# nguyenly.net
KiCad netlist of a schematic drawn in Altium Designer
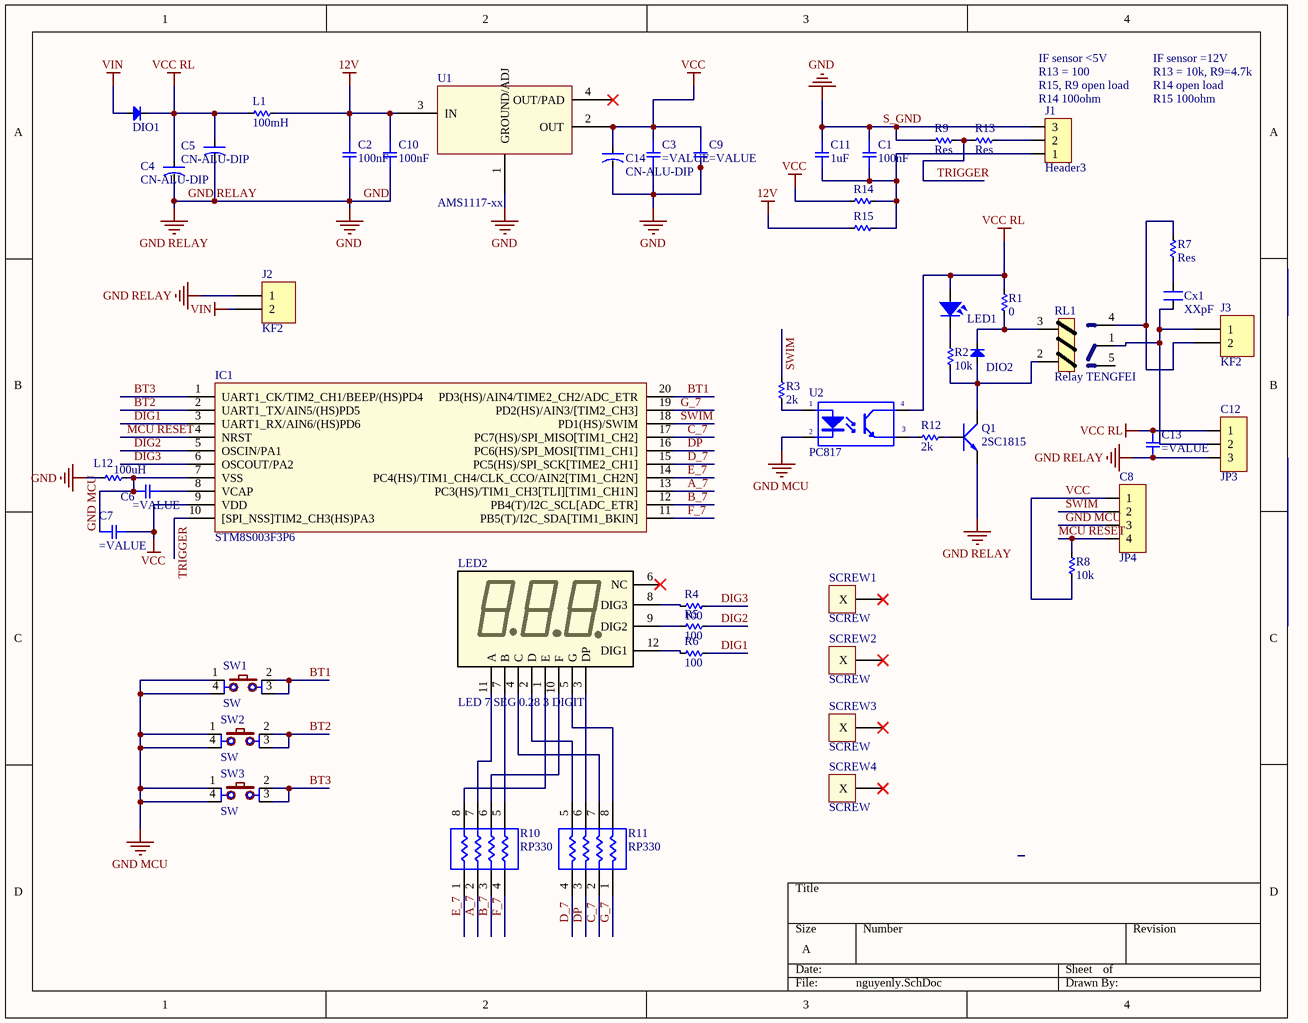
[diagram p0: nguyenly.SchDoc]

(export (version "E")
  (design (tool "Eeschema 10.0.6"))
  (components
    (comp (ref "C1")
      (value "100nF")
      (footprint "SMD-0805C")
      (description "CAP MLCC SMT")
      (libsource (lib "HOANG_ANH") (part "CAPACITOR"))
    )
    (comp (ref "C2")
      (value "100nF")
      (footprint "SMD-0805C")
      (description "CAP MLCC SMT")
      (libsource (lib "HOANG_ANH") (part "CAPACITOR"))
    )
    (comp (ref "C3")
      (value "~")
      (footprint "SMD-0805C")
      (description "CAP MLCC SMT")
      (libsource (lib "HOANG_ANH") (part "CAPACITOR"))
    )
    (comp (ref "C4")
      (value "CN-ALU-DIP")
      (footprint "CA-ALU-8")
      (description "Capacitor (Semiconductor SIM Model)")
      (fields (field (name "PUBLISHER") "Altium Limited"))
      (libsource (lib "LIBRARY") (part "CN-ALU-DIP"))
    )
    (comp (ref "C5")
      (value "CN-ALU-DIP")
      (footprint "CA-ALU-8")
      (description "Capacitor (Semiconductor SIM Model)")
      (fields (field (name "PUBLISHER") "Altium Limited"))
      (libsource (lib "LIBRARY") (part "CN-ALU-DIP"))
    )
    (comp (ref "C6")
      (value "~")
      (footprint "SMD-0805C")
      (description "CAP MLCC SMT")
      (libsource (lib "HOANG_ANH") (part "CAPACITOR"))
    )
    (comp (ref "C7")
      (value "~")
      (footprint "SMD-0805C")
      (description "CAP MLCC SMT")
      (libsource (lib "HOANG_ANH") (part "CAPACITOR"))
    )
    (comp (ref "C8")
      (value "JP4")
      (footprint "JP4-C1T")
      (description "WR-PHD 2.54 mm Angled Socket Header")
      (fields
        (field (name "MANUFACTURER") "Würth Elektronik eiSos GmbH")
        (field (name "PARTNO") "613004143121")
        (field (name "CREATED BY") "Karrer Zheng")
      )
      (libsource (lib "LIBRARY") (part "JP4"))
    )
    (comp (ref "C9")
      (value "~")
      (footprint "SMD-0805C")
      (description "CAP MLCC SMT")
      (libsource (lib "HOANG_ANH") (part "CAPACITOR"))
    )
    (comp (ref "C10")
      (value "100nF")
      (footprint "SMD-0805C")
      (description "CAP MLCC SMT")
      (libsource (lib "HOANG_ANH") (part "CAPACITOR"))
    )
    (comp (ref "C11")
      (value "1uF")
      (footprint "SMD-0805C")
      (description "CAP MLCC SMT")
      (libsource (lib "HOANG_ANH") (part "CAPACITOR"))
    )
    (comp (ref "C12")
      (value "JP3")
      (footprint "JP3-CLOSED")
      (description "WR-PHD 2.54 mm Angled Socket Header")
      (fields
        (field (name "MANUFACTURER") "Würth Elektronik eiSos GmbH")
        (field (name "PARTNO") "613003143121")
        (field (name "CREATED BY") "Karrer Zheng")
      )
      (libsource (lib "LIBRARY") (part "JP3"))
    )
    (comp (ref "C13")
      (value "~")
      (footprint "SMD-1812 FUSE")
      (description "CAP MLCC SMT")
      (libsource (lib "HOANG_ANH") (part "CAPACITOR"))
    )
    (comp (ref "C14")
      (value "CN-ALU-DIP")
      (footprint "CA-ALU-2.54")
      (description "Capacitor (Semiconductor SIM Model)")
      (fields (field (name "PUBLISHER") "Altium Limited"))
      (libsource (lib "LIBRARY") (part "CN-ALU-DIP"))
    )
    (comp (ref "Cx1") (value "XXpF") (footprint "CN2.5") (libsource (lib "LIBRARY") (part "CN")))
    (comp (ref "DIO1")
      (value "Diode SMD")
      (footprint "DIO-SMD-106")
      (description "Default Diode")
      (fields (field (name "PUBLISHER") "Altium Limited"))
      (libsource (lib "LIBRARY") (part "Diode SMD"))
    )
    (comp (ref "DIO2")
      (value "Diode SMD")
      (footprint "DIO-SMD-106")
      (description "Default Diode")
      (fields (field (name "PUBLISHER") "Altium Limited"))
      (libsource (lib "LIBRARY") (part "Diode SMD"))
    )
    (comp (ref "IC1")
      (value "STM8S003F3P6")
      (footprint "TSSOP20")
      (description "MCU 8BIT  8KB FLASH TSSOP-20")
      (fields (field (name "COPYRIGHT BY") "VanDungEvn"))
      (libsource (lib "LIBRARY") (part "STM8S003F3P6"))
    )
    (comp (ref "J1")
      (value "Header3")
      (footprint "Header3")
      (description "Header IDC, 3 x 1 Pin Vertical 2.54mm Pitch (Non-Boxed, Male)")
      (fields
        (field (name "MANUFACTURER") "Würth Elektronik eiSos GmbH")
        (field (name "PARTNO") "613002143121")
        (field (name "CREATED BY") "Karrer Zheng")
      )
      (libsource (lib "LIBRARY") (part "Header3"))
    )
    (comp (ref "J2")
      (value "KF2")
      (footprint "KF2-5.08")
      (fields
        (field (name "MANUFACTURER") "Würth Elektronik eiSos GmbH")
        (field (name "PARTNO") "691103110002")
        (field (name "CREATED BY") "Karrer Zheng")
      )
      (libsource (lib "LIBRARY") (part "KF2"))
    )
    (comp (ref "J3")
      (value "KF2")
      (footprint "KF2-5.08")
      (fields
        (field (name "MANUFACTURER") "Würth Elektronik eiSos GmbH")
        (field (name "PARTNO") "691103110002")
        (field (name "CREATED BY") "Karrer Zheng")
      )
      (libsource (lib "LIBRARY") (part "KF2"))
    )
    (comp (ref "L1")
      (value "100mH")
      (footprint "RES-SMD-0805")
      (description "Resistor")
      (fields
        (field (name "MANUFACTURER") "Generic Components")
        (field (name "PUBLISHER") "Altium Hobart Technology Centre")
      )
      (libsource (lib "LIBRARY") (part "Res-SMD"))
    )
    (comp (ref "L12")
      (value "100uH")
      (footprint "RES-SMD-0805")
      (description "Resistor")
      (fields
        (field (name "MANUFACTURER") "Generic Components")
        (field (name "PUBLISHER") "Altium Hobart Technology Centre")
      )
      (libsource (lib "LIBRARY") (part "Res-SMD"))
    )
    (comp (ref "LED1")
      (value "LED")
      (footprint "LED-0805-Yellow")
      (libsource (lib "LIBRARY") (part "LED SMD"))
    )
    (comp (ref "LED2")
      (value "LED 7 SEG 0.28 3 DIGIT")
      (footprint "LED 7 Seg 0.28, 3 digit, RED")
      (libsource (lib "HOANG_ANH") (part "LED 7 Segment"))
    )
    (comp (ref "Q1")
      (value "2SC1815")
      (footprint "SOT23-321")
      (description "NPN 600mW, ECB")
      (libsource (lib "LIBRARY") (part "2SC1815"))
    )
    (comp (ref "R1")
      (value "0")
      (footprint "RES-SMD-0805")
      (description "Resistor")
      (fields
        (field (name "MANUFACTURER") "Generic Components")
        (field (name "PUBLISHER") "Altium Hobart Technology Centre")
      )
      (libsource (lib "LIBRARY") (part "Res-SMD"))
    )
    (comp (ref "R2")
      (value "10k")
      (footprint "RES-SMD-0805")
      (description "Resistor")
      (fields
        (field (name "MANUFACTURER") "Generic Components")
        (field (name "PUBLISHER") "Altium Hobart Technology Centre")
      )
      (libsource (lib "LIBRARY") (part "Res-SMD"))
    )
    (comp (ref "R3")
      (value "2k")
      (footprint "RES-SMD-0805")
      (description "Resistor")
      (fields
        (field (name "MANUFACTURER") "Generic Components")
        (field (name "PUBLISHER") "Altium Hobart Technology Centre")
      )
      (libsource (lib "LIBRARY") (part "Res-SMD"))
    )
    (comp (ref "R4")
      (value "100")
      (footprint "RES-SMD-0805")
      (description "Resistor")
      (fields
        (field (name "MANUFACTURER") "Generic Components")
        (field (name "PUBLISHER") "Altium Hobart Technology Centre")
      )
      (libsource (lib "LIBRARY") (part "Res-SMD"))
    )
    (comp (ref "R5")
      (value "100")
      (footprint "RES-SMD-0805")
      (description "Resistor")
      (fields
        (field (name "MANUFACTURER") "Generic Components")
        (field (name "PUBLISHER") "Altium Hobart Technology Centre")
      )
      (libsource (lib "LIBRARY") (part "Res-SMD"))
    )
    (comp (ref "R6")
      (value "100")
      (footprint "RES-SMD-0805")
      (description "Resistor")
      (fields
        (field (name "MANUFACTURER") "Generic Components")
        (field (name "PUBLISHER") "Altium Hobart Technology Centre")
      )
      (libsource (lib "LIBRARY") (part "Res-SMD"))
    )
    (comp (ref "R7")
      (value "Res")
      (footprint "RES-SMD-0805")
      (description "Resistor")
      (fields
        (field (name "MANUFACTURER") "Generic Components")
        (field (name "PUBLISHER") "Altium Hobart Technology Centre")
      )
      (libsource (lib "LIBRARY") (part "Res-SMD"))
    )
    (comp (ref "R8")
      (value "10k")
      (footprint "RES-SMD-0805")
      (description "Resistor")
      (fields
        (field (name "MANUFACTURER") "Generic Components")
        (field (name "PUBLISHER") "Altium Hobart Technology Centre")
      )
      (libsource (lib "LIBRARY") (part "Res-SMD"))
    )
    (comp (ref "R9")
      (value "Res")
      (footprint "RES-SMD-0805")
      (description "Resistor")
      (fields
        (field (name "MANUFACTURER") "Generic Components")
        (field (name "PUBLISHER") "Altium Hobart Technology Centre")
      )
      (libsource (lib "LIBRARY") (part "Res-SMD"))
    )
    (comp (ref "R10") (value "RP330") (footprint "RN4-0805") (libsource (lib "LIBRARY") (part "RN4-Dual")))
    (comp (ref "R11") (value "RP330") (footprint "RN4-0805") (libsource (lib "LIBRARY") (part "RN4-Dual")))
    (comp (ref "R12")
      (value "2k")
      (footprint "RES-SMD-0805")
      (description "Resistor")
      (fields
        (field (name "MANUFACTURER") "Generic Components")
        (field (name "PUBLISHER") "Altium Hobart Technology Centre")
      )
      (libsource (lib "LIBRARY") (part "Res-SMD"))
    )
    (comp (ref "R13")
      (value "Res")
      (footprint "RES-SMD-0805")
      (description "Resistor")
      (fields
        (field (name "MANUFACTURER") "Generic Components")
        (field (name "PUBLISHER") "Altium Hobart Technology Centre")
      )
      (libsource (lib "LIBRARY") (part "Res-SMD"))
    )
    (comp (ref "R14")
      (value "Res")
      (footprint "RES-SMD-0805")
      (description "Resistor")
      (fields
        (field (name "MANUFACTURER") "Generic Components")
        (field (name "PUBLISHER") "Altium Hobart Technology Centre")
      )
      (libsource (lib "LIBRARY") (part "Res-SMD"))
    )
    (comp (ref "R15")
      (value "Res")
      (footprint "RES-SMD-0805")
      (description "Resistor")
      (fields
        (field (name "MANUFACTURER") "Generic Components")
        (field (name "PUBLISHER") "Altium Hobart Technology Centre")
      )
      (libsource (lib "LIBRARY") (part "Res-SMD"))
    )
    (comp (ref "RL1")
      (value "Relay TENGFEI")
      (footprint "JQC-T78-DC12V-A")
      (libsource (lib "HOANG_ANH") (part "Relay TENGFEI"))
    )
    (comp (ref "SCREW1") (value "SCREW") (footprint "SCREW-M5") (libsource (lib "HOANG_ANH") (part "SCREW")))
    (comp (ref "SCREW2") (value "SCREW") (footprint "SCREW-M5") (libsource (lib "HOANG_ANH") (part "SCREW")))
    (comp (ref "SCREW3") (value "SCREW") (footprint "SCREW-M5") (libsource (lib "HOANG_ANH") (part "SCREW")))
    (comp (ref "SCREW4") (value "SCREW") (footprint "SCREW-M5") (libsource (lib "HOANG_ANH") (part "SCREW")))
    (comp (ref "SW1")
      (value "SW")
      (footprint "SW2-DIP")
      (description "Switch button 4 pin")
      (libsource (lib "LIBRARY") (part "SW4"))
    )
    (comp (ref "SW2")
      (value "SW")
      (footprint "SW2-DIP")
      (description "Switch button 4 pin")
      (libsource (lib "LIBRARY") (part "SW4"))
    )
    (comp (ref "SW3")
      (value "SW")
      (footprint "SW2-DIP")
      (description "Switch button 4 pin")
      (libsource (lib "LIBRARY") (part "SW4"))
    )
    (comp (ref "U1")
      (value "AMS1117-xx")
      (footprint "SOT-233")
      (libsource (lib "HOANG_ANH") (part "AMS1117-xx"))
    )
    (comp (ref "U2")
      (value "PC817")
      (footprint "DIP4")
      (description "Single Opto")
      (libsource (lib "LIBRARY") (part "PC817"))
    )
  )
  (nets
    (net (code "1") (name "/A_7") (class "Default")
      (node (ref "IC1") (pin "13") (pinfunction "PC3(HS)/TIM1_CH3[TLI][TIM1_CH1N]_13") (pintype "passive"))
      (node (ref "R10") (pin "2") (pinfunction "2_2") (pintype "passive"))
    )
    (net (code "2") (name "/BT1") (class "Default")
      (node (ref "IC1") (pin "20") (pinfunction "PD3(HS)/AIN4/TIME2_CH2/ADC_ETR_20") (pintype "passive"))
      (node (ref "SW1") (pin "2") (pinfunction "2_2") (pintype "passive"))
      (node (ref "SW1") (pin "3") (pinfunction "3_3") (pintype "passive"))
    )
    (net (code "3") (name "/BT2") (class "Default")
      (node (ref "IC1") (pin "2") (pinfunction "UART1_TX/AIN5/(HS)PD5_2") (pintype "passive"))
      (node (ref "SW2") (pin "2") (pinfunction "2_2") (pintype "passive"))
      (node (ref "SW2") (pin "3") (pinfunction "3_3") (pintype "passive"))
    )
    (net (code "4") (name "/BT3") (class "Default")
      (node (ref "IC1") (pin "1") (pinfunction "UART1_CK/TIM2_CH1/BEEP/(HS)PD4_1") (pintype "passive"))
      (node (ref "SW3") (pin "2") (pinfunction "2_2") (pintype "passive"))
      (node (ref "SW3") (pin "3") (pinfunction "3_3") (pintype "passive"))
    )
    (net (code "5") (name "/B_7") (class "Default")
      (node (ref "IC1") (pin "12") (pinfunction "PB4(T)/I2C_SCL[ADC_ETR]_12") (pintype "passive"))
      (node (ref "R10") (pin "3") (pinfunction "3_3") (pintype "passive"))
    )
    (net (code "6") (name "/C_7") (class "Default")
      (node (ref "IC1") (pin "17") (pinfunction "PC7(HS)/SPI_MISO[TIM1_CH2]_17") (pintype "passive"))
      (node (ref "R11") (pin "2") (pinfunction "2_2") (pintype "passive"))
    )
    (net (code "7") (name "/DIG1") (class "Default")
      (node (ref "IC1") (pin "3") (pinfunction "UART1_RX/AIN6/(HS)PD6_3") (pintype "passive"))
      (node (ref "R6") (pin "1") (pinfunction "1_1") (pintype "passive"))
    )
    (net (code "8") (name "/DIG2") (class "Default")
      (node (ref "IC1") (pin "5") (pinfunction "OSCIN/PA1_5") (pintype "passive"))
      (node (ref "R5") (pin "1") (pinfunction "1_1") (pintype "passive"))
    )
    (net (code "9") (name "/DIG3") (class "Default")
      (node (ref "IC1") (pin "6") (pinfunction "OSCOUT/PA2_6") (pintype "passive"))
      (node (ref "R4") (pin "1") (pinfunction "1_1") (pintype "passive"))
    )
    (net (code "10") (name "/DP") (class "Default")
      (node (ref "IC1") (pin "16") (pinfunction "PC6(HS)/SPI_MOSI[TIM1_CH1]_16") (pintype "passive"))
      (node (ref "R11") (pin "3") (pinfunction "3_3") (pintype "passive"))
    )
    (net (code "11") (name "/D_7") (class "Default")
      (node (ref "IC1") (pin "15") (pinfunction "PC5(HS)/SPI_SCK[TIME2_CH1]_15") (pintype "passive"))
      (node (ref "R11") (pin "4") (pinfunction "4_4") (pintype "passive"))
    )
    (net (code "12") (name "/E_7") (class "Default")
      (node (ref "IC1") (pin "14") (pinfunction "PC4(HS)/TIM1_CH4/CLK_CCO/AIN2[TIM1_CH2N]_14") (pintype "passive"))
      (node (ref "R10") (pin "1") (pinfunction "1_1") (pintype "passive"))
    )
    (net (code "13") (name "/F_7") (class "Default")
      (node (ref "IC1") (pin "11") (pinfunction "PB5(T)/I2C_SDA[TIM1_BKIN]_11") (pintype "passive"))
      (node (ref "R10") (pin "4") (pinfunction "4_4") (pintype "passive"))
    )
    (net (code "14") (name "/G_7") (class "Default")
      (node (ref "IC1") (pin "19") (pinfunction "PD2(HS)/AIN3/[TIM2_CH3]_19") (pintype "passive"))
      (node (ref "R11") (pin "1") (pinfunction "1_1") (pintype "passive"))
    )
    (net (code "15") (name "/MCU RESET") (class "Default")
      (node (ref "C8") (pin "4") (pinfunction "4_4") (pintype "passive"))
      (node (ref "IC1") (pin "4") (pinfunction "NRST_4") (pintype "passive"))
      (node (ref "R8") (pin "2") (pinfunction "2_2") (pintype "passive"))
    )
    (net (code "16") (name "/SWIM") (class "Default")
      (node (ref "C8") (pin "2") (pinfunction "2_2") (pintype "passive"))
      (node (ref "IC1") (pin "18") (pinfunction "PD1(HS)/SWIM_18") (pintype "passive"))
      (node (ref "R3") (pin "2") (pinfunction "2_2") (pintype "passive"))
    )
    (net (code "17") (name "/TRIGGER") (class "Default")
      (node (ref "IC1") (pin "10") (pinfunction "[SPI_NSS]TIM2_CH3(HS)PA3_10") (pintype "passive"))
      (node (ref "R13") (pin "2") (pinfunction "2_2") (pintype "passive"))
      (node (ref "R9") (pin "1") (pinfunction "1_1") (pintype "passive"))
    )
    (net (code "18") (name "12V") (class "Default")
      (node (ref "C10") (pin "1") (pinfunction "1_1") (pintype "passive"))
      (node (ref "C2") (pin "1") (pinfunction "1_1") (pintype "passive"))
      (node (ref "L1") (pin "1") (pinfunction "1_1") (pintype "passive"))
      (node (ref "R15") (pin "2") (pinfunction "2_2") (pintype "passive"))
      (node (ref "U1") (pin "3") (pinfunction "IN_3") (pintype "power_in"))
    )
    (net (code "19") (name "GND") (class "Default")
      (node (ref "C1") (pin "1") (pinfunction "1_1") (pintype "passive"))
      (node (ref "C10") (pin "2") (pinfunction "2_2") (pintype "passive"))
      (node (ref "C11") (pin "1") (pinfunction "1_1") (pintype "passive"))
      (node (ref "C12") (pin "3") (pinfunction "3_3") (pintype "passive"))
      (node (ref "C13") (pin "2") (pinfunction "2_2") (pintype "passive"))
      (node (ref "C14") (pin "2") (pinfunction "2_2") (pintype "passive"))
      (node (ref "C2") (pin "2") (pinfunction "2_2") (pintype "passive"))
      (node (ref "C3") (pin "2") (pinfunction "2_2") (pintype "passive"))
      (node (ref "C4") (pin "2") (pinfunction "2_2") (pintype "passive"))
      (node (ref "C5") (pin "2") (pinfunction "2_2") (pintype "passive"))
      (node (ref "C9") (pin "2") (pinfunction "2_2") (pintype "passive"))
      (node (ref "J1") (pin "3") (pinfunction "3_3") (pintype "passive"))
      (node (ref "J2") (pin "1") (pinfunction "1_1") (pintype "passive"))
      (node (ref "L12") (pin "2") (pinfunction "2_2") (pintype "passive"))
      (node (ref "Q1") (pin "1") (pinfunction "E_1") (pintype "passive"))
      (node (ref "R9") (pin "2") (pinfunction "2_2") (pintype "passive"))
      (node (ref "U1") (pin "1") (pinfunction "GROUND/ADJ_1") (pintype "power_in"))
    )
    (net (code "20") (name "GND MCU") (class "Default")
      (node (ref "C6") (pin "1") (pinfunction "1_1") (pintype "passive"))
      (node (ref "C7") (pin "1") (pinfunction "1_1") (pintype "passive"))
      (node (ref "C8") (pin "3") (pinfunction "3_3") (pintype "passive"))
      (node (ref "IC1") (pin "7") (pinfunction "VSS_7") (pintype "passive"))
      (node (ref "L12") (pin "1") (pinfunction "1_1") (pintype "passive"))
      (node (ref "SW1") (pin "1") (pintype "passive"))
      (node (ref "SW1") (pin "4") (pinfunction "4_4") (pintype "passive"))
      (node (ref "SW2") (pin "1") (pintype "passive"))
      (node (ref "SW2") (pin "4") (pinfunction "4_4") (pintype "passive"))
      (node (ref "SW3") (pin "1") (pintype "passive"))
      (node (ref "SW3") (pin "4") (pinfunction "4_4") (pintype "passive"))
      (node (ref "U2") (pin "2") (pinfunction "K_2") (pintype "passive"))
    )
    (net (code "21") (name "Net-(C1-Pad2)") (class "Default")
      (node (ref "C1") (pin "2") (pinfunction "2_2") (pintype "passive"))
      (node (ref "C11") (pin "2") (pinfunction "2_2") (pintype "passive"))
      (node (ref "J1") (pin "1") (pinfunction "1_1") (pintype "passive"))
      (node (ref "R14") (pin "1") (pinfunction "1_1") (pintype "passive"))
      (node (ref "R15") (pin "1") (pinfunction "1_1") (pintype "passive"))
    )
    (net (code "22") (name "Net-(C12-Pad2)") (class "Default")
      (node (ref "C12") (pin "2") (pinfunction "2_2") (pintype "passive"))
      (node (ref "Cx1") (pin "2") (pinfunction "2_2") (pintype "passive"))
      (node (ref "J3") (pin "1") (pinfunction "1_1") (pintype "passive"))
      (node (ref "RL1") (pin "1") (pinfunction "1_1") (pintype "passive"))
    )
    (net (code "23") (name "Net-(Cx1-Pad1)") (class "Default")
      (node (ref "Cx1") (pin "1") (pinfunction "1_1") (pintype "passive"))
      (node (ref "R7") (pin "2") (pinfunction "2_2") (pintype "passive"))
    )
    (net (code "24") (name "Net-(DIO2-A)") (class "Default")
      (node (ref "DIO2") (pin "1") (pinfunction "A_1") (pintype "passive"))
      (node (ref "Q1") (pin "2") (pinfunction "C_2") (pintype "passive"))
      (node (ref "R2") (pin "2") (pinfunction "2_2") (pintype "passive"))
      (node (ref "RL1") (pin "2") (pinfunction "2_2") (pintype "passive"))
    )
    (net (code "25") (name "Net-(DIO2-K)") (class "Default")
      (node (ref "DIO2") (pin "2") (pinfunction "K_2") (pintype "passive"))
      (node (ref "R1") (pin "1") (pinfunction "1_1") (pintype "passive"))
      (node (ref "RL1") (pin "3") (pinfunction "3_3") (pintype "passive"))
    )
    (net (code "26") (name "Net-(IC1-VCAP)") (class "Default")
      (node (ref "C6") (pin "2") (pinfunction "2_2") (pintype "passive"))
      (node (ref "IC1") (pin "8") (pinfunction "VCAP_8") (pintype "passive"))
    )
    (net (code "27") (name "Net-(J1-Pad2)") (class "Default")
      (node (ref "J1") (pin "2") (pinfunction "2_2") (pintype "passive"))
      (node (ref "R13") (pin "1") (pinfunction "1_1") (pintype "passive"))
    )
    (net (code "28") (name "Net-(J3-Pad2)") (class "Default")
      (node (ref "J3") (pin "2") (pinfunction "2_2") (pintype "passive"))
      (node (ref "R7") (pin "1") (pinfunction "1_1") (pintype "passive"))
      (node (ref "RL1") (pin "4") (pinfunction "4_4") (pintype "passive"))
    )
    (net (code "29") (name "Net-(LED1-Pad2)") (class "Default")
      (node (ref "LED1") (pin "2") (pinfunction "2_2") (pintype "passive"))
      (node (ref "R2") (pin "1") (pinfunction "1_1") (pintype "passive"))
    )
    (net (code "30") (name "Net-(LED2-A)") (class "Default")
      (node (ref "LED2") (pin "11") (pinfunction "A_11") (pintype "passive"))
      (node (ref "R10") (pin "7") (pinfunction "7_7") (pintype "passive"))
    )
    (net (code "31") (name "Net-(LED2-B)") (class "Default")
      (node (ref "LED2") (pin "7") (pinfunction "B_7") (pintype "passive"))
      (node (ref "R10") (pin "5") (pinfunction "5_5") (pintype "passive"))
    )
    (net (code "32") (name "Net-(LED2-C)") (class "Default")
      (node (ref "LED2") (pin "4") (pinfunction "C_4") (pintype "passive"))
      (node (ref "R11") (pin "7") (pinfunction "7_7") (pintype "passive"))
    )
    (net (code "33") (name "Net-(LED2-D)") (class "Default")
      (node (ref "LED2") (pin "2") (pinfunction "D_2") (pintype "passive"))
      (node (ref "R11") (pin "5") (pinfunction "5_5") (pintype "passive"))
    )
    (net (code "34") (name "Net-(LED2-DIG1)") (class "Default")
      (node (ref "LED2") (pin "12") (pinfunction "DIG1_12") (pintype "passive"))
      (node (ref "R6") (pin "2") (pinfunction "2_2") (pintype "passive"))
    )
    (net (code "35") (name "Net-(LED2-DIG2)") (class "Default")
      (node (ref "LED2") (pin "9") (pinfunction "DIG2_9") (pintype "passive"))
      (node (ref "R5") (pin "2") (pinfunction "2_2") (pintype "passive"))
    )
    (net (code "36") (name "Net-(LED2-DIG3)") (class "Default")
      (node (ref "LED2") (pin "8") (pinfunction "DIG3_8") (pintype "passive"))
      (node (ref "R4") (pin "2") (pinfunction "2_2") (pintype "passive"))
    )
    (net (code "37") (name "Net-(LED2-DP)") (class "Default")
      (node (ref "LED2") (pin "3") (pinfunction "DP_3") (pintype "passive"))
      (node (ref "R11") (pin "6") (pinfunction "6_6") (pintype "passive"))
    )
    (net (code "38") (name "Net-(LED2-E)") (class "Default")
      (node (ref "LED2") (pin "1") (pinfunction "E_1") (pintype "passive"))
      (node (ref "R10") (pin "8") (pinfunction "8_8") (pintype "passive"))
    )
    (net (code "39") (name "Net-(LED2-F)") (class "Default")
      (node (ref "LED2") (pin "10") (pinfunction "F_10") (pintype "passive"))
      (node (ref "R10") (pin "6") (pinfunction "6_6") (pintype "passive"))
    )
    (net (code "40") (name "Net-(LED2-G)") (class "Default")
      (node (ref "LED2") (pin "5") (pinfunction "G_5") (pintype "passive"))
      (node (ref "R11") (pin "8") (pinfunction "8_8") (pintype "passive"))
    )
    (net (code "41") (name "Net-(Q1-B)") (class "Default")
      (node (ref "Q1") (pin "3") (pinfunction "B_3") (pintype "passive"))
      (node (ref "R12") (pin "1") (pinfunction "1_1") (pintype "passive"))
    )
    (net (code "42") (name "Net-(U2-A)") (class "Default")
      (node (ref "R3") (pin "1") (pinfunction "1_1") (pintype "passive"))
      (node (ref "U2") (pin "1") (pinfunction "A_1") (pintype "passive"))
    )
    (net (code "43") (name "Net-(U2-E)") (class "Default")
      (node (ref "R12") (pin "2") (pinfunction "2_2") (pintype "passive"))
      (node (ref "U2") (pin "3") (pinfunction "E_3") (pintype "passive"))
    )
    (net (code "44") (name "VCC") (class "Default")
      (node (ref "C14") (pin "1") (pinfunction "1_1") (pintype "passive"))
      (node (ref "C3") (pin "1") (pinfunction "1_1") (pintype "passive"))
      (node (ref "C7") (pin "2") (pinfunction "2_2") (pintype "passive"))
      (node (ref "C8") (pin "1") (pinfunction "1_1") (pintype "passive"))
      (node (ref "C9") (pin "1") (pinfunction "1_1") (pintype "passive"))
      (node (ref "IC1") (pin "9") (pinfunction "VDD_9") (pintype "passive"))
      (node (ref "R14") (pin "2") (pinfunction "2_2") (pintype "passive"))
      (node (ref "R8") (pin "1") (pinfunction "1_1") (pintype "passive"))
      (node (ref "U1") (pin "2") (pinfunction "OUT_2") (pintype "power_in"))
    )
    (net (code "45") (name "VCC RL") (class "Default")
      (node (ref "C12") (pin "1") (pinfunction "1_1") (pintype "passive"))
      (node (ref "C13") (pin "1") (pinfunction "1_1") (pintype "passive"))
      (node (ref "C4") (pin "1") (pinfunction "1_1") (pintype "passive"))
      (node (ref "C5") (pin "1") (pinfunction "1_1") (pintype "passive"))
      (node (ref "DIO1") (pin "2") (pinfunction "K_2") (pintype "passive"))
      (node (ref "L1") (pin "2") (pinfunction "2_2") (pintype "passive"))
      (node (ref "LED1") (pin "1") (pinfunction "1_1") (pintype "passive"))
      (node (ref "R1") (pin "2") (pinfunction "2_2") (pintype "passive"))
      (node (ref "U2") (pin "4") (pinfunction "C_4") (pintype "passive"))
    )
    (net (code "46") (name "VIN") (class "Default")
      (node (ref "DIO1") (pin "1") (pinfunction "A_1") (pintype "passive"))
      (node (ref "J2") (pin "2") (pinfunction "2_2") (pintype "passive"))
    )
    (net (code "47") (name "unconnected-(LED2-NC-Pad6)") (class "Default")
      (node (ref "LED2") (pin "6") (pinfunction "NC_6") (pintype "passive+no_connect"))
    )
    (net (code "48") (name "unconnected-(RL1-Pad5)") (class "Default")
      (node (ref "RL1") (pin "5") (pinfunction "5_5") (pintype "passive"))
    )
    (net (code "49") (name "unconnected-(SCREW1-X-Pad1)") (class "Default")
      (node (ref "SCREW1") (pin "1") (pinfunction "X_1") (pintype "passive+no_connect"))
    )
    (net (code "50") (name "unconnected-(SCREW2-X-Pad1)") (class "Default")
      (node (ref "SCREW2") (pin "1") (pinfunction "X_1") (pintype "passive+no_connect"))
    )
    (net (code "51") (name "unconnected-(SCREW3-X-Pad1)") (class "Default")
      (node (ref "SCREW3") (pin "1") (pinfunction "X_1") (pintype "passive+no_connect"))
    )
    (net (code "52") (name "unconnected-(SCREW4-X-Pad1)") (class "Default")
      (node (ref "SCREW4") (pin "1") (pinfunction "X_1") (pintype "passive+no_connect"))
    )
    (net (code "53") (name "unconnected-(U1-OUT{slash}PAD-Pad4)") (class "Default")
      (node (ref "U1") (pin "4") (pinfunction "OUT/PAD_4") (pintype "power_in+no_connect"))
    )
  )
)
